# rpd_schematic.net
KiCad netlist of a schematic drawn in EAGLE
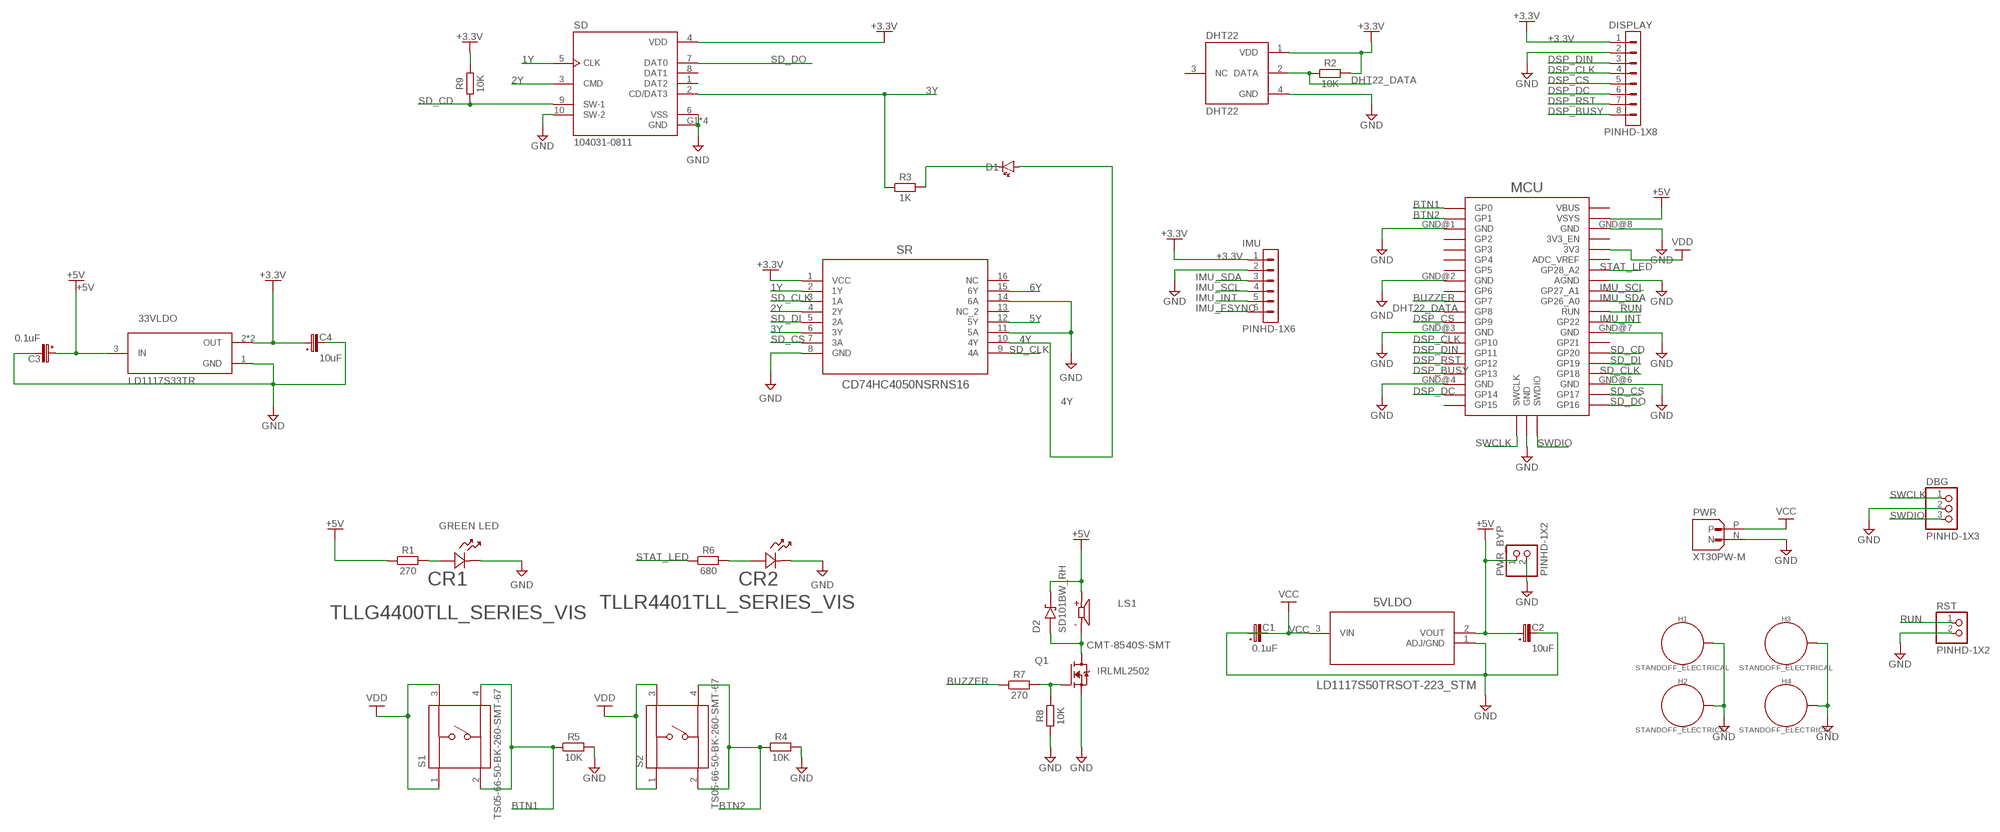
[diagram p0: schematic, sheet 1]

(export (version "E")
  (design (tool "Eeschema 10.0.6"))
  (components
    (comp (ref "5VLDO")
      (value "LD1117S50TRSOT-223_STM")
      (footprint "eagle-import:SOT-223_STM")
      (fields
        (field (name "MANUFACTURER_PART_NUMBER") "LD1117S50TR")
        (field (name "COPYRIGHT") "Copyright (C) 2026 Ultra Librarian. All rights reserved.")
      )
      (libsource (lib "eagle-import") (part "LD1117S50TRSOT-223_STM"))
    )
    (comp (ref "33VLDO")
      (value "LD1117S33TR")
      (footprint "eagle-import:SOT230P700X180-4N")
      (fields (field (name "MANUFACTURER") "ST Microelectronics"))
      (libsource (lib "eagle-import") (part "LD1117S33TR"))
    )
    (comp (ref "C1")
      (value "0.1uF")
      (footprint "eagle-import:CAPMP3216X180N")
      (libsource (lib "eagle-import") (part "C-POLTANTALUM-1206(3216-METRIC)_"))
    )
    (comp (ref "C2")
      (value "10uF")
      (footprint "eagle-import:CAPMP3216X180N")
      (libsource (lib "eagle-import") (part "C-POLTANTALUM-1206(3216-METRIC)_"))
    )
    (comp (ref "C3")
      (value "0.1uF")
      (footprint "eagle-import:CAPMP3216X180N")
      (libsource (lib "eagle-import") (part "C-POLTANTALUM-1206(3216-METRIC)_"))
    )
    (comp (ref "C4")
      (value "10uF")
      (footprint "eagle-import:CAPMP3216X180N")
      (libsource (lib "eagle-import") (part "C-POLTANTALUM-1206(3216-METRIC)_"))
    )
    (comp (ref "CR1")
      (value "TLLG4400TLL_SERIES_VIS")
      (footprint "eagle-import:TLL_SERIES_VIS")
      (description "GREEN LED")
      (fields
        (field (name "MANUFACTURER_PART_NUMBER") "TLLG4400")
        (field (name "COPYRIGHT") "Copyright (C) 2026 Ultra Librarian. All rights reserved.")
      )
      (libsource (lib "eagle-import") (part "TLLG4400TLL_SERIES_VIS"))
    )
    (comp (ref "CR2")
      (value "TLLR4401TLL_SERIES_VIS")
      (footprint "eagle-import:TLL_SERIES_VIS")
      (fields
        (field (name "MANUFACTURER_PART_NUMBER") "TLLR4401")
        (field (name "COPYRIGHT") "Copyright (C) 2026 Ultra Librarian. All rights reserved.")
      )
      (libsource (lib "eagle-import") (part "TLLR4401TLL_SERIES_VIS"))
    )
    (comp (ref "D1")
      (value "LED_RED")
      (footprint "eagle-import:LEDC2012X110N_FLAT-R")
      (libsource (lib "eagle-import") (part "CHIP-FLAT-R_0805"))
    )
    (comp (ref "D2")
      (value "SD101BW_RH")
      (footprint "eagle-import:DIO_SD101BW_RH")
      (fields (field (name "MF") "Taiwan Semiconductor") (field (name "MP") "BAT46GW RHG"))
      (libsource (lib "eagle-import") (part "SD101BW_RH"))
    )
    (comp (ref "DBG")
      (value "PINHD-1X3")
      (footprint "eagle-import:1X03")
      (libsource (lib "eagle-import") (part "PINHD-1X3"))
    )
    (comp (ref "DHT22")
      (value "DHT22")
      (footprint "eagle-import:XDCR_DHT22")
      (fields (field (name "MANUFACTURER") "Aosong Electronics") (field (name "CREATOR") "KARTHIK"))
      (libsource (lib "eagle-import") (part "DHT22"))
    )
    (comp (ref "DISPLAY")
      (value "PINHD-1X8")
      (footprint "eagle-import:1X08")
      (libsource (lib "eagle-import") (part "PINHD-1X8"))
    )
    (comp (ref "H1")
      (value "STANDOFF_ELECTRICAL")
      (footprint "eagle-import:STANDOFF-ELECTRICAL")
      (libsource (lib "eagle-import") (part "STANDOFF_ELECTRICAL"))
    )
    (comp (ref "H2")
      (value "STANDOFF_ELECTRICAL")
      (footprint "eagle-import:STANDOFF-ELECTRICAL")
      (libsource (lib "eagle-import") (part "STANDOFF_ELECTRICAL"))
    )
    (comp (ref "H3")
      (value "STANDOFF_ELECTRICAL")
      (footprint "eagle-import:STANDOFF-ELECTRICAL")
      (libsource (lib "eagle-import") (part "STANDOFF_ELECTRICAL"))
    )
    (comp (ref "H4")
      (value "STANDOFF_ELECTRICAL")
      (footprint "eagle-import:STANDOFF-ELECTRICAL")
      (libsource (lib "eagle-import") (part "STANDOFF_ELECTRICAL"))
    )
    (comp (ref "IMU")
      (value "PINHD-1X6")
      (footprint "eagle-import:1X06")
      (libsource (lib "eagle-import") (part "PINHD-1X6"))
    )
    (comp (ref "LS1")
      (value "CMT-8540S-SMT")
      (footprint "eagle-import:CUI_CMT-8540S-SMT")
      (fields (field (name "MF") "CUI"))
      (libsource (lib "eagle-import") (part "CMT-8540S-SMT"))
    )
    (comp (ref "MCU")
      (value "RPI_PICO_IG-SMD")
      (footprint "eagle-import:RPI_PICO")
      (libsource (lib "eagle-import") (part "RPI_PICO_IG-SMD"))
    )
    (comp (ref "PWR")
      (value "XT30PW-M")
      (footprint "eagle-import:AMASS_XT30PW-M")
      (fields (field (name "MANUFACTURER") "Amass"))
      (libsource (lib "eagle-import") (part "XT30PW-M"))
    )
    (comp (ref "PWR_BYP")
      (value "PINHD-1X2")
      (footprint "eagle-import:1X02")
      (libsource (lib "eagle-import") (part "PINHD-1X2"))
    )
    (comp (ref "Q1")
      (value "IRLML2502")
      (footprint "eagle-import:SOT95P237X112-3N")
      (fields (field (name "MANUFACTURER") "Infineon Technologies"))
      (libsource (lib "eagle-import") (part "IRLML2502"))
    )
    (comp (ref "R1")
      (value "270")
      (footprint "eagle-import:RESC3224X71")
      (libsource (lib "eagle-import") (part "RCHIP-1210(3225-METRIC)_"))
    )
    (comp (ref "R2")
      (value "10K")
      (footprint "eagle-import:RESC3216X70")
      (libsource (lib "eagle-import") (part "RCHIP-1206(3216-METRIC)_"))
    )
    (comp (ref "R3")
      (value "1K")
      (footprint "eagle-import:RESC3216X70")
      (libsource (lib "eagle-import") (part "RCHIP-1206(3216-METRIC)_"))
    )
    (comp (ref "R4")
      (value "10K")
      (footprint "eagle-import:RESC3216X70")
      (libsource (lib "eagle-import") (part "RCHIP-1206(3216-METRIC)_"))
    )
    (comp (ref "R5")
      (value "10K")
      (footprint "eagle-import:RESC3216X70")
      (libsource (lib "eagle-import") (part "RCHIP-1206(3216-METRIC)_"))
    )
    (comp (ref "R6")
      (value "680")
      (footprint "eagle-import:RESC3224X71")
      (libsource (lib "eagle-import") (part "RCHIP-1210(3225-METRIC)_"))
    )
    (comp (ref "R7")
      (value "270")
      (footprint "eagle-import:RESC3224X71")
      (libsource (lib "eagle-import") (part "RCHIP-1210(3225-METRIC)_"))
    )
    (comp (ref "R8")
      (value "10K")
      (footprint "eagle-import:RESC3216X70")
      (libsource (lib "eagle-import") (part "RCHIP-1206(3216-METRIC)_"))
    )
    (comp (ref "R9")
      (value "10K")
      (footprint "eagle-import:RESC3216X70")
      (libsource (lib "eagle-import") (part "RCHIP-1206(3216-METRIC)_"))
    )
    (comp (ref "RST")
      (value "PINHD-1X2")
      (footprint "eagle-import:1X02")
      (libsource (lib "eagle-import") (part "PINHD-1X2"))
    )
    (comp (ref "S1")
      (value "TS05-66-50-BK-260-SMT-67")
      (footprint "eagle-import:SW_TS05-66-50-BK-260-SMT-67")
      (fields (field (name "MANUFACTURER") "CUI Devices"))
      (libsource (lib "eagle-import") (part "TS05-66-50-BK-260-SMT-67"))
    )
    (comp (ref "S2")
      (value "TS05-66-50-BK-260-SMT-67")
      (footprint "eagle-import:SW_TS05-66-50-BK-260-SMT-67")
      (fields (field (name "MANUFACTURER") "CUI Devices"))
      (libsource (lib "eagle-import") (part "TS05-66-50-BK-260-SMT-67"))
    )
    (comp (ref "SD")
      (value "104031-0811")
      (footprint "eagle-import:MOLEX_104031-0811")
      (fields (field (name "MANUFACTURER") "Molex"))
      (libsource (lib "eagle-import") (part "104031-0811"))
    )
    (comp (ref "SR")
      (value "CD74HC4050NSRNS16")
      (footprint "eagle-import:NS16")
      (fields
        (field (name "MANUFACTURER_PART_NUMBER") "CD74HC4050NSR")
        (field (name "COPYRIGHT") "Copyright (C) 2026 Ultra Librarian. All rights reserved.")
      )
      (libsource (lib "eagle-import") (part "CD74HC4050NSRNS16"))
    )
  )
  (nets
    (net (code "1") (name "+3.3V") (class "Default")
      (node (ref "33VLDO") (pin "2") (pinfunction "OUT_2") (pintype "output"))
      (node (ref "33VLDO") (pin "4") (pinfunction "OUT_4") (pintype "output"))
      (node (ref "C4") (pin "1") (pinfunction "+_1") (pintype "passive"))
      (node (ref "DHT22") (pin "1") (pinfunction "VDD_1") (pintype "power_in"))
      (node (ref "DISPLAY") (pin "1") (pinfunction "1_1") (pintype "passive"))
      (node (ref "IMU") (pin "1") (pinfunction "1_1") (pintype "passive"))
      (node (ref "R2") (pin "2") (pinfunction "2_2") (pintype "passive"))
      (node (ref "R9") (pin "2") (pinfunction "2_2") (pintype "passive"))
      (node (ref "SD") (pin "4") (pinfunction "VDD_4") (pintype "power_in"))
      (node (ref "SR") (pin "1") (pinfunction "VCC_1") (pintype "power_in"))
    )
    (net (code "2") (name "+5V") (class "Default")
      (node (ref "33VLDO") (pin "3") (pinfunction "IN_3") (pintype "input"))
      (node (ref "5VLDO") (pin "2") (pinfunction "VOUT_2") (pintype "power_in"))
      (node (ref "C2") (pin "1") (pinfunction "+_1") (pintype "passive"))
      (node (ref "C3") (pin "1") (pinfunction "+_1") (pintype "passive"))
      (node (ref "D2") (pin "C") (pinfunction "K_C") (pintype "passive"))
      (node (ref "LS1") (pin "P") (pinfunction "P_P") (pintype "passive"))
      (node (ref "MCU") (pin "VSYS") (pinfunction "VSYS_VSYS") (pintype "bidirectional"))
      (node (ref "PWR_BYP") (pin "1") (pinfunction "1_1") (pintype "passive"))
      (node (ref "R1") (pin "1") (pinfunction "1_1") (pintype "passive"))
    )
    (net (code "3") (name "/1Y") (class "Default")
      (node (ref "SD") (pin "5") (pinfunction "CLK_5") (pintype "input"))
      (node (ref "SR") (pin "2") (pinfunction "1Y_2") (pintype "output"))
    )
    (net (code "4") (name "/2Y") (class "Default")
      (node (ref "SD") (pin "3") (pinfunction "CMD_3") (pintype "bidirectional"))
      (node (ref "SR") (pin "4") (pinfunction "2Y_4") (pintype "output"))
    )
    (net (code "5") (name "/3Y") (class "Default")
      (node (ref "R3") (pin "1") (pinfunction "1_1") (pintype "passive"))
      (node (ref "SD") (pin "2") (pinfunction "CD/DAT3_2") (pintype "bidirectional"))
      (node (ref "SR") (pin "6") (pinfunction "3Y_6") (pintype "output"))
    )
    (net (code "6") (name "/4Y") (class "Default")
      (node (ref "D1") (pin "A") (pinfunction "A_A") (pintype "passive"))
      (node (ref "SR") (pin "10") (pinfunction "4Y_10") (pintype "output"))
    )
    (net (code "7") (name "/5Y") (class "Default")
      (node (ref "SR") (pin "12") (pinfunction "5Y_12") (pintype "output"))
    )
    (net (code "8") (name "/6Y") (class "Default")
      (node (ref "SR") (pin "15") (pinfunction "6Y_15") (pintype "output"))
    )
    (net (code "9") (name "/BTN1") (class "Default")
      (node (ref "MCU") (pin "GP0") (pinfunction "GP0_GP0") (pintype "bidirectional"))
      (node (ref "R5") (pin "1") (pinfunction "1_1") (pintype "passive"))
      (node (ref "S1") (pin "2") (pinfunction "2_2") (pintype "passive"))
      (node (ref "S1") (pin "4") (pinfunction "4_4") (pintype "passive"))
    )
    (net (code "10") (name "/BTN2") (class "Default")
      (node (ref "MCU") (pin "GP1") (pinfunction "GP1_GP1") (pintype "bidirectional"))
      (node (ref "R4") (pin "1") (pinfunction "1_1") (pintype "passive"))
      (node (ref "S2") (pin "2") (pinfunction "2_2") (pintype "passive"))
      (node (ref "S2") (pin "4") (pinfunction "4_4") (pintype "passive"))
    )
    (net (code "11") (name "/BUZZER") (class "Default")
      (node (ref "MCU") (pin "GP7") (pinfunction "GP7_GP7") (pintype "bidirectional"))
      (node (ref "R7") (pin "1") (pinfunction "1_1") (pintype "passive"))
    )
    (net (code "12") (name "/DHT22_DATA") (class "Default")
      (node (ref "DHT22") (pin "2") (pinfunction "DATA_2") (pintype "bidirectional"))
      (node (ref "MCU") (pin "GP8") (pinfunction "GP8_GP8") (pintype "bidirectional"))
      (node (ref "R2") (pin "1") (pinfunction "1_1") (pintype "passive"))
    )
    (net (code "13") (name "/DSP_BUSY") (class "Default")
      (node (ref "DISPLAY") (pin "8") (pinfunction "8_8") (pintype "passive"))
      (node (ref "MCU") (pin "GP13") (pinfunction "GP13_GP13") (pintype "bidirectional"))
    )
    (net (code "14") (name "/DSP_CLK") (class "Default")
      (node (ref "DISPLAY") (pin "4") (pinfunction "4_4") (pintype "passive"))
      (node (ref "MCU") (pin "GP10") (pinfunction "GP10_GP10") (pintype "bidirectional"))
    )
    (net (code "15") (name "/DSP_CS") (class "Default")
      (node (ref "DISPLAY") (pin "5") (pinfunction "5_5") (pintype "passive"))
      (node (ref "MCU") (pin "GP9") (pinfunction "GP9_GP9") (pintype "bidirectional"))
    )
    (net (code "16") (name "/DSP_DC") (class "Default")
      (node (ref "DISPLAY") (pin "6") (pinfunction "6_6") (pintype "passive"))
      (node (ref "MCU") (pin "GP14") (pinfunction "GP14_GP14") (pintype "bidirectional"))
    )
    (net (code "17") (name "/DSP_DIN") (class "Default")
      (node (ref "DISPLAY") (pin "3") (pinfunction "3_3") (pintype "passive"))
      (node (ref "MCU") (pin "GP11") (pinfunction "GP11_GP11") (pintype "bidirectional"))
    )
    (net (code "18") (name "/DSP_RST") (class "Default")
      (node (ref "DISPLAY") (pin "7") (pinfunction "7_7") (pintype "passive"))
      (node (ref "MCU") (pin "GP12") (pinfunction "GP12_GP12") (pintype "bidirectional"))
    )
    (net (code "19") (name "/IMU_FSYNC") (class "Default")
      (node (ref "IMU") (pin "6") (pinfunction "6_6") (pintype "passive"))
    )
    (net (code "20") (name "/IMU_INT") (class "Default")
      (node (ref "IMU") (pin "5") (pinfunction "5_5") (pintype "passive"))
      (node (ref "MCU") (pin "GP22") (pinfunction "GP22_GP22") (pintype "bidirectional"))
    )
    (net (code "21") (name "/IMU_SCL") (class "Default")
      (node (ref "IMU") (pin "4") (pinfunction "4_4") (pintype "passive"))
      (node (ref "MCU") (pin "GP27_A1") (pinfunction "GP27_A1_GP27_A1") (pintype "bidirectional"))
    )
    (net (code "22") (name "/IMU_SDA") (class "Default")
      (node (ref "IMU") (pin "3") (pinfunction "3_3") (pintype "passive"))
      (node (ref "MCU") (pin "GP26_A0") (pinfunction "GP26_A0_GP26_A0") (pintype "bidirectional"))
    )
    (net (code "23") (name "/RUN") (class "Default")
      (node (ref "MCU") (pin "RUN") (pinfunction "RUN_RUN") (pintype "bidirectional"))
      (node (ref "RST") (pin "1") (pinfunction "1_1") (pintype "passive"))
    )
    (net (code "24") (name "/SD_CD") (class "Default")
      (node (ref "MCU") (pin "GP20") (pinfunction "GP20_GP20") (pintype "bidirectional"))
      (node (ref "R9") (pin "1") (pinfunction "1_1") (pintype "passive"))
      (node (ref "SD") (pin "9") (pinfunction "SW-1_9") (pintype "passive"))
    )
    (net (code "25") (name "/SD_CLK") (class "Default")
      (node (ref "MCU") (pin "GP18") (pinfunction "GP18_GP18") (pintype "bidirectional"))
      (node (ref "SR") (pin "3") (pinfunction "1A_3") (pintype "input"))
      (node (ref "SR") (pin "9") (pinfunction "4A_9") (pintype "input"))
    )
    (net (code "26") (name "/SD_CS") (class "Default")
      (node (ref "MCU") (pin "GP17") (pinfunction "GP17_GP17") (pintype "bidirectional"))
      (node (ref "SR") (pin "7") (pinfunction "3A_7") (pintype "input"))
    )
    (net (code "27") (name "/SD_DI") (class "Default")
      (node (ref "MCU") (pin "GP19") (pinfunction "GP19_GP19") (pintype "bidirectional"))
      (node (ref "SR") (pin "5") (pinfunction "2A_5") (pintype "input"))
    )
    (net (code "28") (name "/SD_DO") (class "Default")
      (node (ref "MCU") (pin "GP16") (pinfunction "GP16_GP16") (pintype "bidirectional"))
      (node (ref "SD") (pin "7") (pinfunction "DAT0_7") (pintype "bidirectional"))
    )
    (net (code "29") (name "/STAT_LED") (class "Default")
      (node (ref "MCU") (pin "GP28_A2") (pinfunction "GP28_A2_GP28_A2") (pintype "bidirectional"))
      (node (ref "R6") (pin "1") (pinfunction "1_1") (pintype "passive"))
    )
    (net (code "30") (name "/SWCLK") (class "Default")
      (node (ref "DBG") (pin "1") (pinfunction "1_1") (pintype "passive"))
      (node (ref "MCU") (pin "SWCLK") (pinfunction "SWCLK_SWCLK") (pintype "bidirectional"))
    )
    (net (code "31") (name "/SWDIO") (class "Default")
      (node (ref "DBG") (pin "3") (pinfunction "3_3") (pintype "passive"))
      (node (ref "MCU") (pin "SWDIO") (pinfunction "SWDIO_SWDIO") (pintype "bidirectional"))
    )
    (net (code "32") (name "GND") (class "Default")
      (node (ref "33VLDO") (pin "1") (pinfunction "GND_1") (pintype "power_in"))
      (node (ref "5VLDO") (pin "1") (pinfunction "ADJ/GND_1") (pintype "passive"))
      (node (ref "C1") (pin "2") (pinfunction "-_2") (pintype "passive"))
      (node (ref "C2") (pin "2") (pinfunction "-_2") (pintype "passive"))
      (node (ref "C3") (pin "2") (pinfunction "-_2") (pintype "passive"))
      (node (ref "C4") (pin "2") (pinfunction "-_2") (pintype "passive"))
      (node (ref "CR1") (pin "1") (pinfunction "1_1") (pintype "passive"))
      (node (ref "CR2") (pin "1") (pinfunction "1_1") (pintype "passive"))
      (node (ref "DBG") (pin "2") (pinfunction "2_2") (pintype "passive"))
      (node (ref "DHT22") (pin "4") (pinfunction "GND_4") (pintype "power_in"))
      (node (ref "DISPLAY") (pin "2") (pinfunction "2_2") (pintype "passive"))
      (node (ref "H1") (pin "P1") (pinfunction "P$1_P1") (pintype "bidirectional"))
      (node (ref "H2") (pin "P1") (pinfunction "P$1_P1") (pintype "bidirectional"))
      (node (ref "H3") (pin "P1") (pinfunction "P$1_P1") (pintype "bidirectional"))
      (node (ref "H4") (pin "P1") (pinfunction "P$1_P1") (pintype "bidirectional"))
      (node (ref "IMU") (pin "2") (pinfunction "2_2") (pintype "passive"))
      (node (ref "MCU") (pin "AGND") (pinfunction "AGND_AGND") (pintype "bidirectional"))
      (node (ref "MCU") (pin "GND@1") (pinfunction "GND_GND@1") (pintype "bidirectional"))
      (node (ref "MCU") (pin "GND@2") (pinfunction "GND_GND@2") (pintype "bidirectional"))
      (node (ref "MCU") (pin "GND@3") (pinfunction "GND_GND@3") (pintype "bidirectional"))
      (node (ref "MCU") (pin "GND@4") (pinfunction "GND_GND@4") (pintype "bidirectional"))
      (node (ref "MCU") (pin "GND@5") (pinfunction "GND_GND@5") (pintype "bidirectional"))
      (node (ref "MCU") (pin "GND@6") (pinfunction "GND_GND@6") (pintype "bidirectional"))
      (node (ref "MCU") (pin "GND@7") (pinfunction "GND_GND@7") (pintype "bidirectional"))
      (node (ref "MCU") (pin "GND@8") (pinfunction "GND_GND@8") (pintype "bidirectional"))
      (node (ref "PWR") (pin "N") (pinfunction "N_N") (pintype "power_in"))
      (node (ref "PWR_BYP") (pin "2") (pinfunction "2_2") (pintype "passive"))
      (node (ref "Q1") (pin "2") (pinfunction "S_2") (pintype "passive"))
      (node (ref "R4") (pin "2") (pinfunction "2_2") (pintype "passive"))
      (node (ref "R5") (pin "2") (pinfunction "2_2") (pintype "passive"))
      (node (ref "R8") (pin "1") (pinfunction "1_1") (pintype "passive"))
      (node (ref "RST") (pin "2") (pinfunction "2_2") (pintype "passive"))
      (node (ref "SD") (pin "10") (pinfunction "SW-2_10") (pintype "passive"))
      (node (ref "SD") (pin "6") (pinfunction "VSS_6") (pintype "power_in"))
      (node (ref "SD") (pin "G1") (pinfunction "GND_G1") (pintype "power_in"))
      (node (ref "SD") (pin "G2") (pinfunction "GND_G2") (pintype "power_in"))
      (node (ref "SD") (pin "G3") (pinfunction "GND_G3") (pintype "power_in"))
      (node (ref "SD") (pin "G4") (pinfunction "GND_G4") (pintype "power_in"))
      (node (ref "SR") (pin "11") (pinfunction "5A_11") (pintype "input"))
      (node (ref "SR") (pin "14") (pinfunction "6A_14") (pintype "input"))
      (node (ref "SR") (pin "8") (pinfunction "GND_8") (pintype "power_in"))
    )
    (net (code "33") (name "Net-(CR1-Pad2)") (class "Default")
      (node (ref "CR1") (pin "2") (pinfunction "2_2") (pintype "passive"))
      (node (ref "R1") (pin "2") (pinfunction "2_2") (pintype "passive"))
    )
    (net (code "34") (name "Net-(CR2-Pad2)") (class "Default")
      (node (ref "CR2") (pin "2") (pinfunction "2_2") (pintype "passive"))
      (node (ref "R6") (pin "2") (pinfunction "2_2") (pintype "passive"))
    )
    (net (code "35") (name "Net-(D1-PadC)") (class "Default")
      (node (ref "D1") (pin "C") (pinfunction "C_C") (pintype "passive"))
      (node (ref "R3") (pin "2") (pinfunction "2_2") (pintype "passive"))
    )
    (net (code "36") (name "Net-(Q1-D)") (class "Default")
      (node (ref "D2") (pin "A") (pinfunction "A_A") (pintype "passive"))
      (node (ref "LS1") (pin "N") (pinfunction "N_N") (pintype "passive"))
      (node (ref "Q1") (pin "3") (pinfunction "D_3") (pintype "passive"))
    )
    (net (code "37") (name "Net-(Q1-G)") (class "Default")
      (node (ref "Q1") (pin "1") (pinfunction "G_1") (pintype "passive"))
      (node (ref "R7") (pin "2") (pinfunction "2_2") (pintype "passive"))
      (node (ref "R8") (pin "2") (pinfunction "2_2") (pintype "passive"))
    )
    (net (code "38") (name "VCC") (class "Default")
      (node (ref "5VLDO") (pin "3") (pinfunction "VIN_3") (pintype "power_in"))
      (node (ref "C1") (pin "1") (pinfunction "+_1") (pintype "passive"))
      (node (ref "PWR") (pin "P") (pinfunction "P_P") (pintype "power_in"))
    )
    (net (code "39") (name "VDD") (class "Default")
      (node (ref "MCU") (pin "3V3") (pinfunction "3V3_3V3") (pintype "bidirectional"))
      (node (ref "S1") (pin "1") (pinfunction "1_1") (pintype "passive"))
      (node (ref "S1") (pin "3") (pinfunction "3_3") (pintype "passive"))
      (node (ref "S2") (pin "1") (pinfunction "1_1") (pintype "passive"))
      (node (ref "S2") (pin "3") (pinfunction "3_3") (pintype "passive"))
    )
    (net (code "40") (name "unconnected-(DHT22-NC-Pad3)") (class "Default")
      (node (ref "DHT22") (pin "3") (pinfunction "NC_3") (pintype "no_connect"))
    )
    (net (code "41") (name "unconnected-(MCU-Pad3V3_EN)") (class "Default")
      (node (ref "MCU") (pin "3V3_EN") (pinfunction "3V3_EN_3V3_EN") (pintype "bidirectional"))
    )
    (net (code "42") (name "unconnected-(MCU-PadADC_VREF)") (class "Default")
      (node (ref "MCU") (pin "ADC_VREF") (pinfunction "ADC_VREF_ADC_VREF") (pintype "bidirectional"))
    )
    (net (code "43") (name "unconnected-(MCU-PadGP2)") (class "Default")
      (node (ref "MCU") (pin "GP2") (pinfunction "GP2_GP2") (pintype "bidirectional"))
    )
    (net (code "44") (name "unconnected-(MCU-PadGP3)") (class "Default")
      (node (ref "MCU") (pin "GP3") (pinfunction "GP3_GP3") (pintype "bidirectional"))
    )
    (net (code "45") (name "unconnected-(MCU-PadGP4)") (class "Default")
      (node (ref "MCU") (pin "GP4") (pinfunction "GP4_GP4") (pintype "bidirectional"))
    )
    (net (code "46") (name "unconnected-(MCU-PadGP5)") (class "Default")
      (node (ref "MCU") (pin "GP5") (pinfunction "GP5_GP5") (pintype "bidirectional"))
    )
    (net (code "47") (name "unconnected-(MCU-PadGP6)") (class "Default")
      (node (ref "MCU") (pin "GP6") (pinfunction "GP6_GP6") (pintype "bidirectional"))
    )
    (net (code "48") (name "unconnected-(MCU-PadGP15)") (class "Default")
      (node (ref "MCU") (pin "GP15") (pinfunction "GP15_GP15") (pintype "bidirectional"))
    )
    (net (code "49") (name "unconnected-(MCU-PadGP21)") (class "Default")
      (node (ref "MCU") (pin "GP21") (pinfunction "GP21_GP21") (pintype "bidirectional"))
    )
    (net (code "50") (name "unconnected-(MCU-PadVBUS)") (class "Default")
      (node (ref "MCU") (pin "VBUS") (pinfunction "VBUS_VBUS") (pintype "bidirectional"))
    )
    (net (code "51") (name "unconnected-(SD-DAT1-Pad8)") (class "Default")
      (node (ref "SD") (pin "8") (pinfunction "DAT1_8") (pintype "bidirectional"))
    )
    (net (code "52") (name "unconnected-(SD-DAT2-Pad1)") (class "Default")
      (node (ref "SD") (pin "1") (pinfunction "DAT2_1") (pintype "bidirectional"))
    )
    (net (code "53") (name "unconnected-(SR-NC-Pad16)") (class "Default")
      (node (ref "SR") (pin "16") (pinfunction "NC_16") (pintype "no_connect"))
    )
    (net (code "54") (name "unconnected-(SR-NC_2-Pad13)") (class "Default")
      (node (ref "SR") (pin "13") (pinfunction "NC_2_13") (pintype "no_connect"))
    )
  )
)
